# MarsCarrier_PWR.net
KiCad netlist of a schematic drawn in Altium Designer
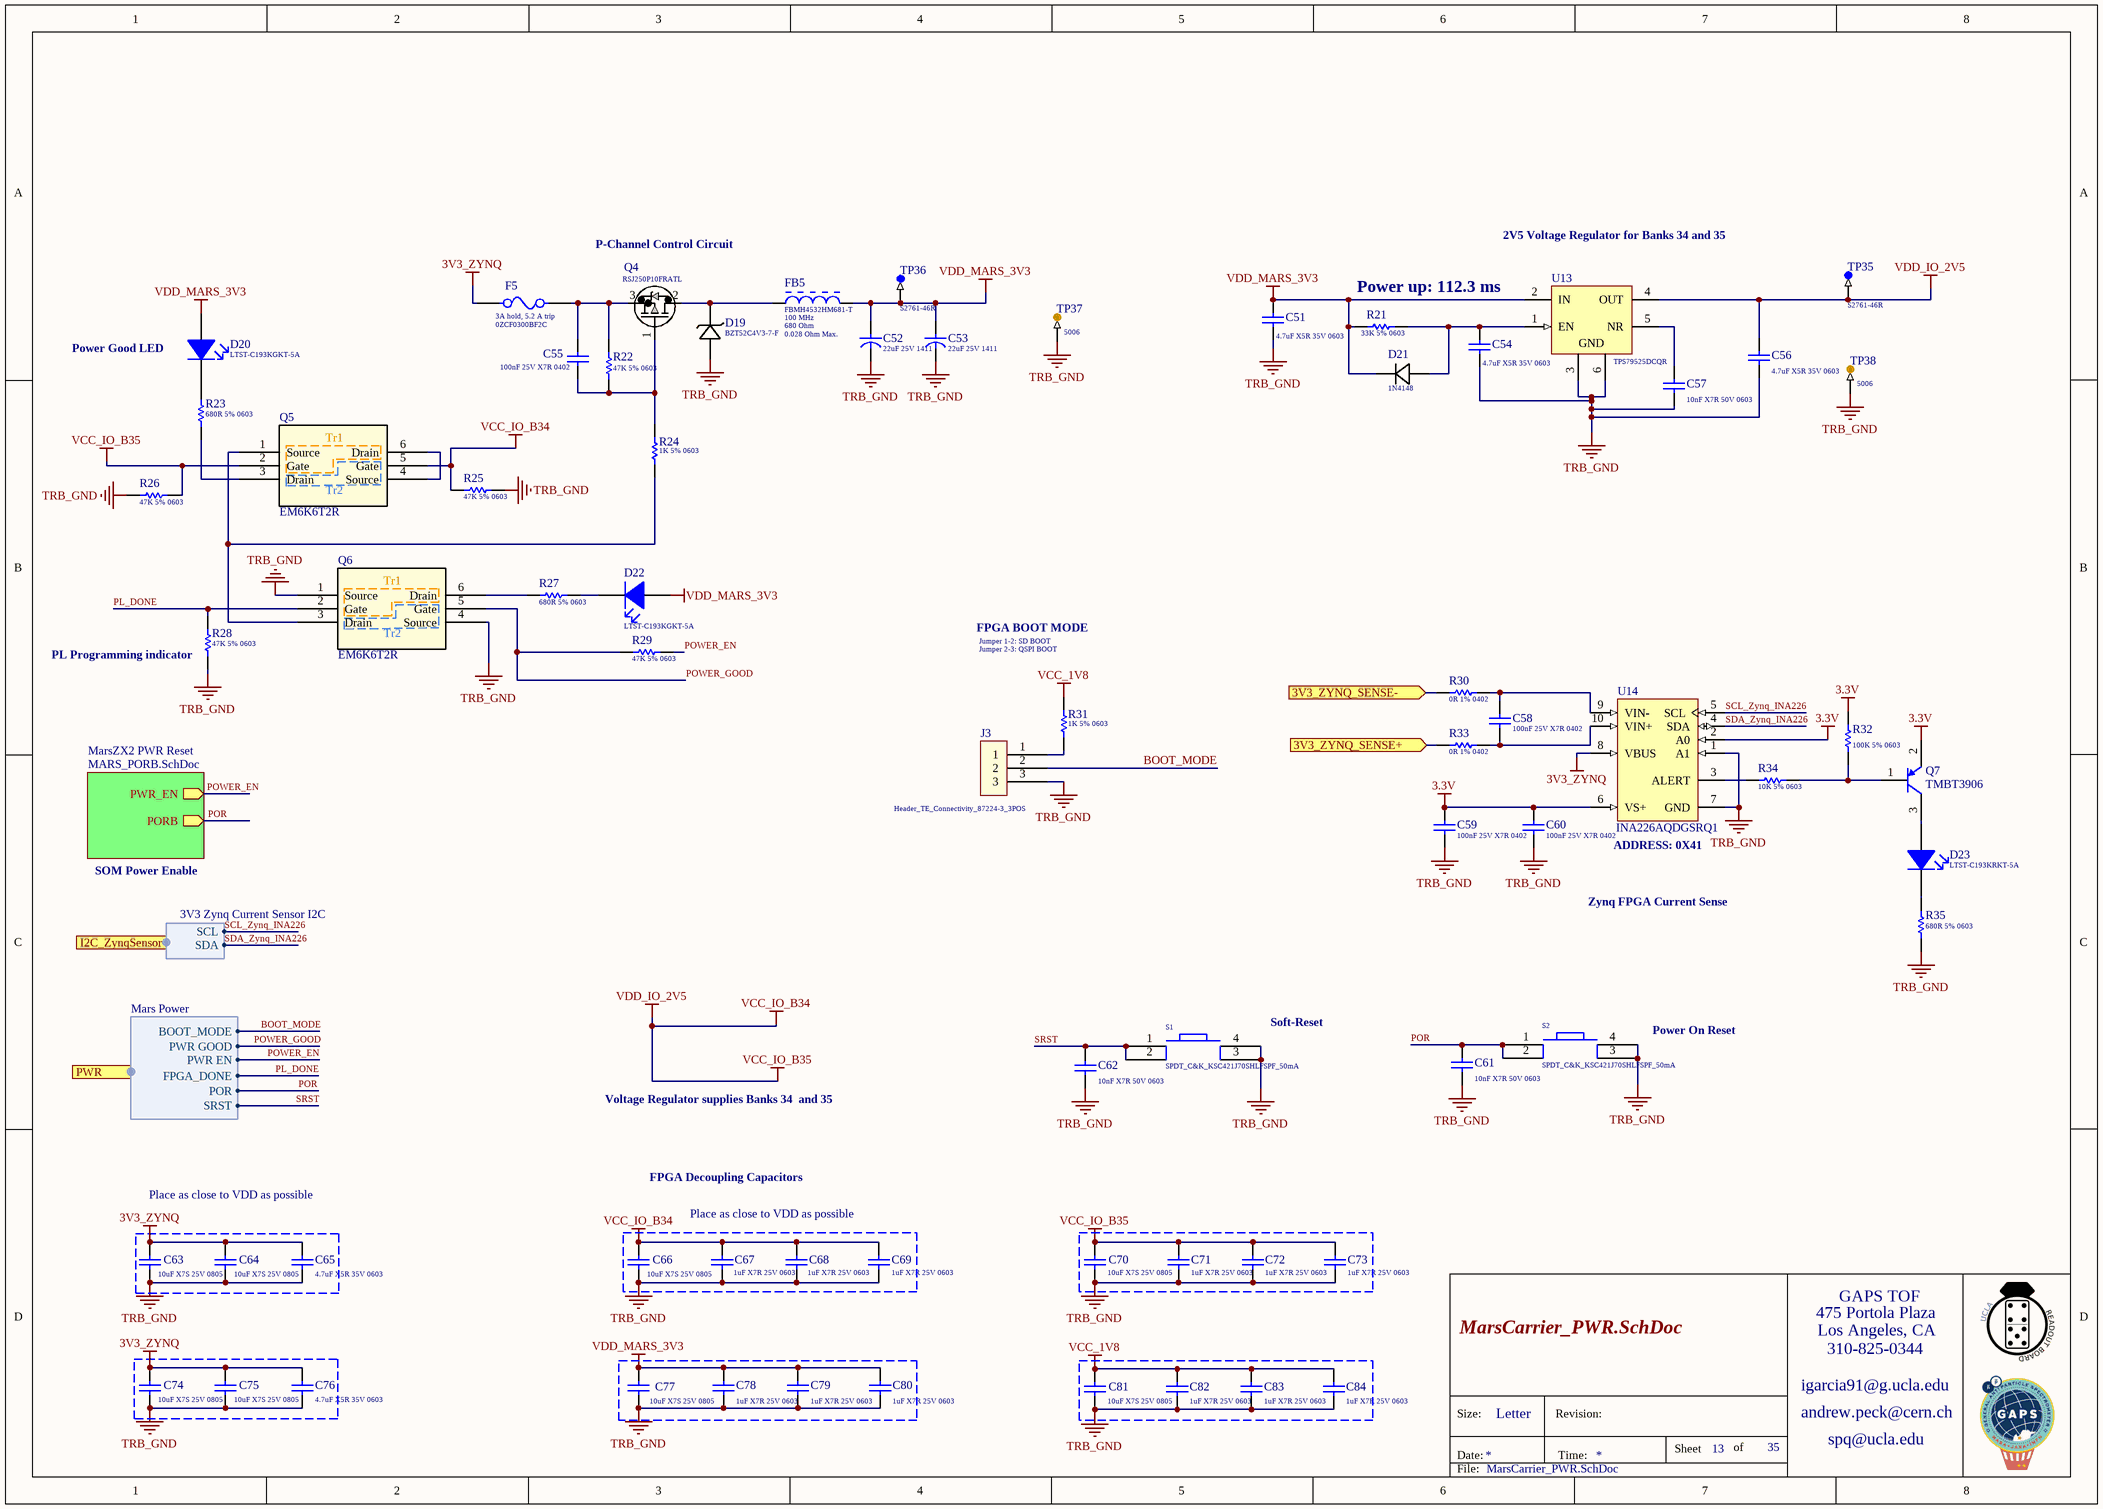
[diagram p0: MarsCarrier_PWR.SchDoc]

(export (version "E")
  (design (tool "Eeschema 10.0.6"))
  (components
    (comp (ref "C51")
      (value "Cap_Murata_ZRB18AR6YA475ME05L_4.7uF")
      (footprint "Cap_Murata_ZRB18AR6YA475ME05L_4.7uF")
      (description "CAP CER 4.7uF 35V X5R 0603")
      (fields (field (name "CAPACITANCE") "4.7uF X5R 35V 0603"))
      (libsource (lib "Cap_Murata_ZRB18AR6YA475ME05L_4.7uF") (part "Cap_Murata_ZRB18AR6YA475ME05L_4.7uF"))
    )
    (comp (ref "C52")
      (value "Cap_Kemet_T521B226M025ATE100_22uF")
      (footprint "Cap_Kemet_T521B226M025ATE100_22uF")
      (description "Tantalum Capacitors - Polymer SMD 25V 22uF 1311 20% ESR=100mOhms")
      (fields (field (name "CAPACITANCE") "22uF 25V 1411"))
      (libsource (lib "Cap_Kemet_T521B226M025ATE100_22uF") (part "Cap_Kemet_T521B226M025ATE100_22uF"))
    )
    (comp (ref "C53")
      (value "Cap_Kemet_T521B226M025ATE100_22uF")
      (footprint "Cap_Kemet_T521B226M025ATE100_22uF")
      (description "Tantalum Capacitors - Polymer SMD 25V 22uF 1311 20% ESR=100mOhms")
      (fields (field (name "CAPACITANCE") "22uF 25V 1411"))
      (libsource (lib "Cap_Kemet_T521B226M025ATE100_22uF") (part "Cap_Kemet_T521B226M025ATE100_22uF"))
    )
    (comp (ref "C54")
      (value "Cap_Murata_ZRB18AR6YA475ME05L_4.7uF")
      (footprint "Cap_Murata_ZRB18AR6YA475ME05L_4.7uF")
      (description "CAP CER 4.7uF 35V X5R 0603")
      (fields (field (name "CAPACITANCE") "4.7uF X5R 35V 0603"))
      (libsource (lib "Cap_Murata_ZRB18AR6YA475ME05L_4.7uF") (part "Cap_Murata_ZRB18AR6YA475ME05L_4.7uF"))
    )
    (comp (ref "C55")
      (value "Cap_Taiyo_Yuden_TMK105B7104KV-FR_100nF")
      (footprint "Cap_Taiyo_Yuden_TMK105B7104KV-FR_100nF")
      (description "CAP CER 100nF 25V X7R 0402")
      (fields (field (name "CAPACITANCE") "100nF 25V X7R 0402"))
      (libsource (lib "Cap_Taiyo_Yuden_TMK105B7104KV-FR_100nF") (part "Cap_Taiyo_Yuden_TMK105B7104KV-FR_100nF"))
    )
    (comp (ref "C56")
      (value "Cap_Murata_ZRB18AR6YA475ME05L_4.7uF")
      (footprint "Cap_Murata_ZRB18AR6YA475ME05L_4.7uF")
      (description "CAP CER 4.7uF 35V X5R 0603")
      (fields (field (name "CAPACITANCE") "4.7uF X5R 35V 0603"))
      (libsource (lib "Cap_Murata_ZRB18AR6YA475ME05L_4.7uF") (part "Cap_Murata_ZRB18AR6YA475ME05L_4.7uF"))
    )
    (comp (ref "C57")
      (value "Cap_Kemet_C0603C103J5RACTU_eec")
      (footprint "Kemet_C0603_0")
      (description "CAP CER 10nF 50V X7R 0603")
      (fields
        (field (name "PART NUMBER") "C0603C103J5RACTU")
        (field (name "MANUFACTURER") "Kemet")
        (field (name "CAPACITANCE") "10nF X7R 50V 0603")
      )
      (libsource (lib "Cap_Kemet_C0603C103J5RACTU_10nF") (part "Cap_Kemet_C0603C103J5RACTU_eec"))
    )
    (comp (ref "C58")
      (value "Cap_Taiyo_Yuden_TMK105B7104KV-FR_100nF")
      (footprint "Cap_Taiyo_Yuden_TMK105B7104KV-FR_100nF")
      (description "CAP CER 100nF 25V X7R 0402")
      (fields (field (name "CAPACITANCE") "100nF 25V X7R 0402"))
      (libsource (lib "Cap_Taiyo_Yuden_TMK105B7104KV-FR_100nF") (part "Cap_Taiyo_Yuden_TMK105B7104KV-FR_100nF"))
    )
    (comp (ref "C59")
      (value "Cap_Taiyo_Yuden_TMK105B7104KV-FR_100nF")
      (footprint "Cap_Taiyo_Yuden_TMK105B7104KV-FR_100nF")
      (description "CAP CER 100nF 25V X7R 0402")
      (fields (field (name "CAPACITANCE") "100nF 25V X7R 0402"))
      (libsource (lib "Cap_Taiyo_Yuden_TMK105B7104KV-FR_100nF") (part "Cap_Taiyo_Yuden_TMK105B7104KV-FR_100nF"))
    )
    (comp (ref "C60")
      (value "Cap_Taiyo_Yuden_TMK105B7104KV-FR_100nF")
      (footprint "Cap_Taiyo_Yuden_TMK105B7104KV-FR_100nF")
      (description "CAP CER 100nF 25V X7R 0402")
      (fields (field (name "CAPACITANCE") "100nF 25V X7R 0402"))
      (libsource (lib "Cap_Taiyo_Yuden_TMK105B7104KV-FR_100nF") (part "Cap_Taiyo_Yuden_TMK105B7104KV-FR_100nF"))
    )
    (comp (ref "C61")
      (value "Cap_Kemet_C0603C103J5RACTU_eec")
      (footprint "Kemet_C0603_0")
      (description "CAP CER 10nF 50V X7R 0603")
      (fields
        (field (name "PART NUMBER") "C0603C103J5RACTU")
        (field (name "MANUFACTURER") "Kemet")
        (field (name "CAPACITANCE") "10nF X7R 50V 0603")
      )
      (libsource (lib "Cap_Kemet_C0603C103J5RACTU_10nF") (part "Cap_Kemet_C0603C103J5RACTU_eec"))
    )
    (comp (ref "C62")
      (value "Cap_Kemet_C0603C103J5RACTU_eec")
      (footprint "Kemet_C0603_0")
      (description "CAP CER 10nF 50V X7R 0603")
      (fields
        (field (name "PART NUMBER") "C0603C103J5RACTU")
        (field (name "MANUFACTURER") "Kemet")
        (field (name "CAPACITANCE") "10nF X7R 50V 0603")
      )
      (libsource (lib "Cap_Kemet_C0603C103J5RACTU_10nF") (part "Cap_Kemet_C0603C103J5RACTU_eec"))
    )
    (comp (ref "C63")
      (value "Cap_Murata_ GRM21BC71E106ME11L_10uF")
      (footprint "Cap_Murata_ GRM21BC71E106ME11L_10uF")
      (description "CAP CER 10uF 25V X7R 0805")
      (fields (field (name "CAPACITANCE") "10uF X7S 25V 0805"))
      (libsource (lib "Cap_Murata_ GRM21BC71E106ME11L_10uF") (part "Cap_Murata_ GRM21BC71E106ME11L_10uF"))
    )
    (comp (ref "C64")
      (value "Cap_Murata_ GRM21BC71E106ME11L_10uF")
      (footprint "Cap_Murata_ GRM21BC71E106ME11L_10uF")
      (description "CAP CER 10uF 25V X7R 0805")
      (fields (field (name "CAPACITANCE") "10uF X7S 25V 0805"))
      (libsource (lib "Cap_Murata_ GRM21BC71E106ME11L_10uF") (part "Cap_Murata_ GRM21BC71E106ME11L_10uF"))
    )
    (comp (ref "C65")
      (value "Cap_Murata_ZRB18AR6YA475ME05L_4.7uF")
      (footprint "Cap_Murata_ZRB18AR6YA475ME05L_4.7uF")
      (description "CAP CER 4.7uF 35V X5R 0603")
      (fields (field (name "CAPACITANCE") "4.7uF X5R 35V 0603"))
      (libsource (lib "Cap_Murata_ZRB18AR6YA475ME05L_4.7uF") (part "Cap_Murata_ZRB18AR6YA475ME05L_4.7uF"))
    )
    (comp (ref "C66")
      (value "Cap_Murata_ GRM21BC71E106ME11L_10uF")
      (footprint "Cap_Murata_ GRM21BC71E106ME11L_10uF")
      (description "CAP CER 10uF 25V X7R 0805")
      (fields (field (name "CAPACITANCE") "10uF X7S 25V 0805"))
      (libsource (lib "Cap_Murata_ GRM21BC71E106ME11L_10uF") (part "Cap_Murata_ GRM21BC71E106ME11L_10uF"))
    )
    (comp (ref "C67")
      (value "Cap_Murata_GCJ188R71E105KA01J_1uF")
      (footprint "Cap_Murata_GCJ188R71E105KA01J_1uF")
      (description "CAP CER 1uF 25V X7R 0603")
      (fields (field (name "CAPACITANCE") "1uF X7R 25V 0603"))
      (libsource (lib "Cap_Murata_GCJ188R71E105KA01J_1uF") (part "Cap_Murata_GCJ188R71E105KA01J_1uF"))
    )
    (comp (ref "C68")
      (value "Cap_Murata_GCJ188R71E105KA01J_1uF")
      (footprint "Cap_Murata_GCJ188R71E105KA01J_1uF")
      (description "CAP CER 1uF 25V X7R 0603")
      (fields (field (name "CAPACITANCE") "1uF X7R 25V 0603"))
      (libsource (lib "Cap_Murata_GCJ188R71E105KA01J_1uF") (part "Cap_Murata_GCJ188R71E105KA01J_1uF"))
    )
    (comp (ref "C69")
      (value "Cap_Murata_GCJ188R71E105KA01J_1uF")
      (footprint "Cap_Murata_GCJ188R71E105KA01J_1uF")
      (description "CAP CER 1uF 25V X7R 0603")
      (fields (field (name "CAPACITANCE") "1uF X7R 25V 0603"))
      (libsource (lib "Cap_Murata_GCJ188R71E105KA01J_1uF") (part "Cap_Murata_GCJ188R71E105KA01J_1uF"))
    )
    (comp (ref "C70")
      (value "Cap_Murata_ GRM21BC71E106ME11L_10uF")
      (footprint "Cap_Murata_ GRM21BC71E106ME11L_10uF")
      (description "CAP CER 10uF 25V X7R 0805")
      (fields (field (name "CAPACITANCE") "10uF X7S 25V 0805"))
      (libsource (lib "Cap_Murata_ GRM21BC71E106ME11L_10uF") (part "Cap_Murata_ GRM21BC71E106ME11L_10uF"))
    )
    (comp (ref "C71")
      (value "Cap_Murata_GCJ188R71E105KA01J_1uF")
      (footprint "Cap_Murata_GCJ188R71E105KA01J_1uF")
      (description "CAP CER 1uF 25V X7R 0603")
      (fields (field (name "CAPACITANCE") "1uF X7R 25V 0603"))
      (libsource (lib "Cap_Murata_GCJ188R71E105KA01J_1uF") (part "Cap_Murata_GCJ188R71E105KA01J_1uF"))
    )
    (comp (ref "C72")
      (value "Cap_Murata_GCJ188R71E105KA01J_1uF")
      (footprint "Cap_Murata_GCJ188R71E105KA01J_1uF")
      (description "CAP CER 1uF 25V X7R 0603")
      (fields (field (name "CAPACITANCE") "1uF X7R 25V 0603"))
      (libsource (lib "Cap_Murata_GCJ188R71E105KA01J_1uF") (part "Cap_Murata_GCJ188R71E105KA01J_1uF"))
    )
    (comp (ref "C73")
      (value "Cap_Murata_GCJ188R71E105KA01J_1uF")
      (footprint "Cap_Murata_GCJ188R71E105KA01J_1uF")
      (description "CAP CER 1uF 25V X7R 0603")
      (fields (field (name "CAPACITANCE") "1uF X7R 25V 0603"))
      (libsource (lib "Cap_Murata_GCJ188R71E105KA01J_1uF") (part "Cap_Murata_GCJ188R71E105KA01J_1uF"))
    )
    (comp (ref "C74")
      (value "Cap_Murata_ GRM21BC71E106ME11L_10uF")
      (footprint "Cap_Murata_ GRM21BC71E106ME11L_10uF")
      (description "CAP CER 10uF 25V X7R 0805")
      (fields (field (name "CAPACITANCE") "10uF X7S 25V 0805"))
      (libsource (lib "Cap_Murata_ GRM21BC71E106ME11L_10uF") (part "Cap_Murata_ GRM21BC71E106ME11L_10uF"))
    )
    (comp (ref "C75")
      (value "Cap_Murata_ GRM21BC71E106ME11L_10uF")
      (footprint "Cap_Murata_ GRM21BC71E106ME11L_10uF")
      (description "CAP CER 10uF 25V X7R 0805")
      (fields (field (name "CAPACITANCE") "10uF X7S 25V 0805"))
      (libsource (lib "Cap_Murata_ GRM21BC71E106ME11L_10uF") (part "Cap_Murata_ GRM21BC71E106ME11L_10uF"))
    )
    (comp (ref "C76")
      (value "Cap_Murata_ZRB18AR6YA475ME05L_4.7uF")
      (footprint "Cap_Murata_ZRB18AR6YA475ME05L_4.7uF")
      (description "CAP CER 4.7uF 35V X5R 0603")
      (fields (field (name "CAPACITANCE") "4.7uF X5R 35V 0603"))
      (libsource (lib "Cap_Murata_ZRB18AR6YA475ME05L_4.7uF") (part "Cap_Murata_ZRB18AR6YA475ME05L_4.7uF"))
    )
    (comp (ref "C77")
      (value "Cap_Murata_ GRM21BC71E106ME11L_10uF")
      (footprint "Cap_Murata_ GRM21BC71E106ME11L_10uF")
      (description "CAP CER 10uF 25V X7R 0805")
      (fields (field (name "CAPACITANCE") "10uF X7S 25V 0805"))
      (libsource (lib "Cap_Murata_ GRM21BC71E106ME11L_10uF") (part "Cap_Murata_ GRM21BC71E106ME11L_10uF"))
    )
    (comp (ref "C78")
      (value "Cap_Murata_GCJ188R71E105KA01J_1uF")
      (footprint "Cap_Murata_GCJ188R71E105KA01J_1uF")
      (description "CAP CER 1uF 25V X7R 0603")
      (fields (field (name "CAPACITANCE") "1uF X7R 25V 0603"))
      (libsource (lib "Cap_Murata_GCJ188R71E105KA01J_1uF") (part "Cap_Murata_GCJ188R71E105KA01J_1uF"))
    )
    (comp (ref "C79")
      (value "Cap_Murata_GCJ188R71E105KA01J_1uF")
      (footprint "Cap_Murata_GCJ188R71E105KA01J_1uF")
      (description "CAP CER 1uF 25V X7R 0603")
      (fields (field (name "CAPACITANCE") "1uF X7R 25V 0603"))
      (libsource (lib "Cap_Murata_GCJ188R71E105KA01J_1uF") (part "Cap_Murata_GCJ188R71E105KA01J_1uF"))
    )
    (comp (ref "C80")
      (value "Cap_Murata_GCJ188R71E105KA01J_1uF")
      (footprint "Cap_Murata_GCJ188R71E105KA01J_1uF")
      (description "CAP CER 1uF 25V X7R 0603")
      (fields (field (name "CAPACITANCE") "1uF X7R 25V 0603"))
      (libsource (lib "Cap_Murata_GCJ188R71E105KA01J_1uF") (part "Cap_Murata_GCJ188R71E105KA01J_1uF"))
    )
    (comp (ref "C81")
      (value "Cap_Murata_ GRM21BC71E106ME11L_10uF")
      (footprint "Cap_Murata_ GRM21BC71E106ME11L_10uF")
      (description "CAP CER 10uF 25V X7R 0805")
      (fields (field (name "CAPACITANCE") "10uF X7S 25V 0805"))
      (libsource (lib "Cap_Murata_ GRM21BC71E106ME11L_10uF") (part "Cap_Murata_ GRM21BC71E106ME11L_10uF"))
    )
    (comp (ref "C82")
      (value "Cap_Murata_GCJ188R71E105KA01J_1uF")
      (footprint "Cap_Murata_GCJ188R71E105KA01J_1uF")
      (description "CAP CER 1uF 25V X7R 0603")
      (fields (field (name "CAPACITANCE") "1uF X7R 25V 0603"))
      (libsource (lib "Cap_Murata_GCJ188R71E105KA01J_1uF") (part "Cap_Murata_GCJ188R71E105KA01J_1uF"))
    )
    (comp (ref "C83")
      (value "Cap_Murata_GCJ188R71E105KA01J_1uF")
      (footprint "Cap_Murata_GCJ188R71E105KA01J_1uF")
      (description "CAP CER 1uF 25V X7R 0603")
      (fields (field (name "CAPACITANCE") "1uF X7R 25V 0603"))
      (libsource (lib "Cap_Murata_GCJ188R71E105KA01J_1uF") (part "Cap_Murata_GCJ188R71E105KA01J_1uF"))
    )
    (comp (ref "C84")
      (value "Cap_Murata_GCJ188R71E105KA01J_1uF")
      (footprint "Cap_Murata_GCJ188R71E105KA01J_1uF")
      (description "CAP CER 1uF 25V X7R 0603")
      (fields (field (name "CAPACITANCE") "1uF X7R 25V 0603"))
      (libsource (lib "Cap_Murata_GCJ188R71E105KA01J_1uF") (part "Cap_Murata_GCJ188R71E105KA01J_1uF"))
    )
    (comp (ref "D19")
      (value "BZT52C4V3-7-F")
      (footprint "SOD123")
      (description "Zener Diodes 500mW 4.3V Zener AEC-Q101 Qualified")
      (fields (field (name "SERIES") "BZT52C4V3-7-F"))
      (libsource (lib "4v3_zener_BZT52C4V3-7-F") (part "BZT52C4V3-7-F"))
    )
    (comp (ref "D20")
      (value "Led_Lite-On_LTST-C193KGKT-5A_Green")
      (footprint "Led_Lite-On_LTST-C193KGKT-5A_Green")
      (description "Standard LEDs - SMD Green 470nm 28mcd 20mA")
      (fields (field (name "SERIES") "LTST-C193KGKT-5A"))
      (libsource (lib "Led_Lite-On_LTST-C193KGKT-5A_Green") (part "Led_Lite-On_LTST-C193KGKT-5A_Green"))
    )
    (comp (ref "D21")
      (value "Diode_ON_Semiconductor_1N4148WT_300mA")
      (footprint "Diode_ON_Semiconductor_1N4148WT_300mA")
      (description "Diodes - General Purpose, Power, Switching SINGLE JUNC. 75V 4.0NS COMP")
      (fields (field (name "SERIES") "1N4148"))
      (libsource (lib "Diode_ON_Semiconductor_1N4148WT_300mA") (part "Diode_ON_Semiconductor_1N4148WT_300mA"))
    )
    (comp (ref "D22")
      (value "Led_Lite-On_LTST-C193KGKT-5A_Green")
      (footprint "Led_Lite-On_LTST-C193KGKT-5A_Green")
      (description "Standard LEDs - SMD Green 470nm 28mcd 20mA")
      (fields (field (name "SERIES") "LTST-C193KGKT-5A"))
      (libsource (lib "Led_Lite-On_LTST-C193KGKT-5A_Green") (part "Led_Lite-On_LTST-C193KGKT-5A_Green"))
    )
    (comp (ref "D23")
      (value "LTST-C193KRKT-5A")
      (footprint "Led_Lite-On_LTST-C193KGKT-5A_Red")
      (description "Standard LEDs - SMD Red 470nm 28mcd 20mA")
      (fields (field (name "SERIES") "LTST-C193KRKT-5A"))
      (libsource (lib "Led_Lite-On_LTST-C193KGKT-5A_Red") (part "Led_Lite-On_LTST-C193KGKT-5A_Red"))
    )
    (comp (ref "F5")
      (value "3A hold, 5.2 A trip")
      (footprint "Bel_0ZCF_MFG")
      (description "Resettable Fuses - PPTC 3A 24V PPTC 2920 SMD")
      (fields (field (name "SERIES") "0ZCF0300BF2C"))
      (libsource (lib "Fuse_Bel_0ZCF0300BF2C_3A_hold") (part "0ZCF0300BF2C"))
    )
    (comp (ref "FB5")
      (value "FBMH4532HM681-T")
      (footprint "TAYO-FBMH4532-2_V")
      (fields
        (field (name "PARTNUMBER") "FBMH4532HM681-T")
        (field (name "MANUFACTURER") "Taiyo Yuden")
        (field (name "MEASURING FREQUENCY") "100 MHz")
        (field (name "NOMINAL IMPEDANCE") "680 Ohm")
        (field (name "DC RESISTANCE") "0.028 Ohm Max.")
      )
      (libsource (lib "Taiyo_Yuden_FBMH4532HM681") (part "FBMH4532HM681-T"))
    )
    (comp (ref "J3")
      (value "Header_TE_Connectivity_87224-3_3POS")
      (footprint "Header_TE_Connectivity_87224-3_3POS")
      (description "Headers & Wire Housings UNSHRD VERT SNGL 3")
      (libsource (lib "Header_TE_Connectivity_87224-3_3POS") (part "Header_TE_Connectivity_87224-3_3POS"))
    )
    (comp (ref "Q4")
      (value "Mos_ROHM_RSJ250P10FRATL_25A")
      (footprint "Mos_ROHM_RSJ250P10FRATL_25A")
      (description "MOSFET Pch -100V Vds -25A 0.05Rds(on) 60Qg")
      (fields (field (name "SERIES") "RSJ250P10FRATL"))
      (libsource (lib "Mos_ROHM_RSJ250P10FRATL_25A") (part "Mos_ROHM_RSJ250P10FRATL_25A"))
    )
    (comp (ref "Q5")
      (value "EM6K6T2R")
      (footprint "TRANS_EM6_ROM")
      (description "MOSFET Small Signal Dual N-CH 20V .3A .15W")
      (libsource (lib "Trans_NFET_ROHM_EM6K6T2R") (part "EM6K6T2R"))
    )
    (comp (ref "Q6")
      (value "EM6K6T2R")
      (footprint "TRANS_EM6_ROM")
      (description "MOSFET Small Signal Dual N-CH 20V .3A .15W")
      (libsource (lib "Trans_NFET_ROHM_EM6K6T2R") (part "EM6K6T2R"))
    )
    (comp (ref "Q7")
      (value "BJT_PNP_Toshiba_TMBT3906")
      (footprint "BJT_PNP_Toshiba_TMBT3906")
      (description "Bipolar Transistors - BJT Transistor for Low Freq. Amplification")
      (fields (field (name "SERIES") "TMBT3906") (field (name "MANUFACTURER") "Toshiba"))
      (libsource (lib "BJT_PNP_Toshiba_TMBT3906") (part "BJT_PNP_Toshiba_TMBT3906"))
    )
    (comp (ref "R21")
      (value "33K 5% 0603")
      (footprint "RESC0603(1608)_L")
      (description "33K 0.1W 5% 0603 (1608 Metric)  SMD")
      (fields (field (name "TOLERANCE") "5 %") (field (name "POWER") "0.1 W"))
      (libsource (lib "Altium Content Vault") (part "RES"))
    )
    (comp (ref "R22")
      (value "47K 5% 0603")
      (footprint "RESC0603(1608)_L")
      (description "47K 0.1W 5% 0603 (1608 Metric)  SMD")
      (fields (field (name "TOLERANCE") "5 %") (field (name "POWER") "0.1 W"))
      (libsource (lib "Altium Content Vault") (part "RES"))
    )
    (comp (ref "R23")
      (value "680R 5% 0603")
      (footprint "RESC0603(1608)_L")
      (description "680R 0.1W 5% 0603 (1608 Metric)  SMD")
      (fields (field (name "TOLERANCE") "5 %") (field (name "POWER") "0.1 W"))
      (libsource (lib "Altium Content Vault") (part "RES"))
    )
    (comp (ref "R24")
      (value "1K 5% 0603")
      (footprint "RESC0603(1608)_L")
      (description "1K 0.1W 5% 0603 (1608 Metric)  SMD")
      (fields (field (name "TOLERANCE") "5 %") (field (name "POWER") "0.1 W"))
      (libsource (lib "Altium Content Vault") (part "RES"))
    )
    (comp (ref "R25")
      (value "47K 5% 0603")
      (footprint "RESC0603(1608)_L")
      (description "47K 0.1W 5% 0603 (1608 Metric)  SMD")
      (fields (field (name "TOLERANCE") "5 %") (field (name "POWER") "0.1 W"))
      (libsource (lib "Altium Content Vault") (part "RES"))
    )
    (comp (ref "R26")
      (value "47K 5% 0603")
      (footprint "RESC0603(1608)_L")
      (description "47K 0.1W 5% 0603 (1608 Metric)  SMD")
      (fields (field (name "TOLERANCE") "5 %") (field (name "POWER") "0.1 W"))
      (libsource (lib "Altium Content Vault") (part "RES"))
    )
    (comp (ref "R27")
      (value "680R 5% 0603")
      (footprint "RESC0603(1608)_L")
      (description "680R 0.1W 5% 0603 (1608 Metric)  SMD")
      (fields (field (name "TOLERANCE") "5 %") (field (name "POWER") "0.1 W"))
      (libsource (lib "Altium Content Vault") (part "RES"))
    )
    (comp (ref "R28")
      (value "47K 5% 0603")
      (footprint "RESC0603(1608)_L")
      (description "47K 0.1W 5% 0603 (1608 Metric)  SMD")
      (fields (field (name "TOLERANCE") "5 %") (field (name "POWER") "0.1 W"))
      (libsource (lib "Altium Content Vault") (part "RES"))
    )
    (comp (ref "R29")
      (value "47K 5% 0603")
      (footprint "RESC0603(1608)_L")
      (description "47K 0.1W 5% 0603 (1608 Metric)  SMD")
      (fields (field (name "TOLERANCE") "5 %") (field (name "POWER") "0.1 W"))
      (libsource (lib "Altium Content Vault") (part "RES"))
    )
    (comp (ref "R30")
      (value "Res_Vishay_CRCW04020000Z0EDC_0_Ohm")
      (footprint "Res_Vishay_CRCW04020000Z0EDC_0_Ohm")
      (description "0R 0.062W 1% 0402 (1005 Metric)  SMD")
      (fields (field (name "RESISTANCE") "0R 1% 0402"))
      (libsource (lib "Res_Vishay_CRCW04020000Z0EDC_0_Ohm") (part "Res_Vishay_CRCW04020000Z0EDC_0_Ohm"))
    )
    (comp (ref "R31")
      (value "1K 5% 0603")
      (footprint "RESC0603(1608)_L")
      (description "1K 0.1W 5% 0603 (1608 Metric)  SMD")
      (fields (field (name "TOLERANCE") "5 %") (field (name "POWER") "0.1 W"))
      (libsource (lib "Altium Content Vault") (part "RES"))
    )
    (comp (ref "R32")
      (value "100K 5% 0603")
      (footprint "RESC0603(1608)_N")
      (description "100K 0.1W 5% 0603 (1608 Metric)  SMD")
      (fields (field (name "TOLERANCE") "5 %") (field (name "POWER") "0.1 W"))
      (libsource (lib "Altium Content Vault") (part "RES"))
    )
    (comp (ref "R33")
      (value "Res_Vishay_CRCW04020000Z0EDC_0_Ohm")
      (footprint "Res_Vishay_CRCW04020000Z0EDC_0_Ohm")
      (description "0R 0.062W 1% 0402 (1005 Metric)  SMD")
      (fields (field (name "RESISTANCE") "0R 1% 0402"))
      (libsource (lib "Res_Vishay_CRCW04020000Z0EDC_0_Ohm") (part "Res_Vishay_CRCW04020000Z0EDC_0_Ohm"))
    )
    (comp (ref "R34")
      (value "10K 5% 0603")
      (footprint "RESC0603(1608)_L")
      (description "10K 0.1W 5% 0603 (1608 Metric)  SMD")
      (fields (field (name "TOLERANCE") "5 %") (field (name "POWER") "0.1 W"))
      (libsource (lib "Altium Content Vault") (part "RES"))
    )
    (comp (ref "R35")
      (value "680R 5% 0603")
      (footprint "RESC0603(1608)_L")
      (description "680R 0.1W 5% 0603 (1608 Metric)  SMD")
      (fields (field (name "TOLERANCE") "5 %") (field (name "POWER") "0.1 W"))
      (libsource (lib "Altium Content Vault") (part "RES"))
    )
    (comp (ref "S1")
      (value "SPDT_C&K_KSC421J70SHLFSPF_50mA")
      (footprint "SPDT_C&K_KSC421J70SHLFSPF_50mA")
      (description "Tactile Switches Tact 6.2 x 6.2, 5.1 mm H, 1.7N, J leads, Potting Friendly, IP67")
      (libsource (lib "SPDT_C&K_KSC421J70SHLFSPF_50mA") (part "SPDT_C&K_KSC421J70SHLFSPF_50mA"))
    )
    (comp (ref "S2")
      (value "SPDT_C&K_KSC421J70SHLFSPF_50mA")
      (footprint "SPDT_C&K_KSC421J70SHLFSPF_50mA")
      (description "Tactile Switches Tact 6.2 x 6.2, 5.1 mm H, 1.7N, J leads, Potting Friendly, IP67")
      (libsource (lib "SPDT_C&K_KSC421J70SHLFSPF_50mA") (part "SPDT_C&K_KSC421J70SHLFSPF_50mA"))
    )
    (comp (ref "TP35")
      (value "TP_Harwin_S2761_46R")
      (footprint "TP_Harwin_S2761_46R")
      (description "Circuit Board Hardware - PCB SMT Mini Test Terminal, Reel")
      (fields (field (name "SERIES") "S2761-46R"))
      (libsource (lib "TP_Harwin_S2761_46R") (part "TP_Harwin_S2761_46R"))
    )
    (comp (ref "TP36")
      (value "TP_Harwin_S2761_46R")
      (footprint "TP_Harwin_S2761_46R")
      (description "Circuit Board Hardware - PCB SMT Mini Test Terminal, Reel")
      (fields (field (name "SERIES") "S2761-46R"))
      (libsource (lib "TP_Harwin_S2761_46R") (part "TP_Harwin_S2761_46R"))
    )
    (comp (ref "TP37")
      (value "TP_Keystone_Electronics_5006")
      (footprint "TP_Keystone_Electronics_5006")
      (description "Circuit Board Hardware - PCB TEST POINT BLK .063")
      (fields (field (name "SERIES") "5006"))
      (libsource (lib "TP_Keystone_Electronics_5006") (part "TP_Keystone_Electronics_5006"))
    )
    (comp (ref "TP38")
      (value "TP_Keystone_Electronics_5006")
      (footprint "TP_Keystone_Electronics_5006")
      (description "Circuit Board Hardware - PCB TEST POINT BLK .063")
      (fields (field (name "SERIES") "5006"))
      (libsource (lib "TP_Keystone_Electronics_5006") (part "TP_Keystone_Electronics_5006"))
    )
    (comp (ref "U13")
      (value "TPS79525DCQR")
      (footprint "DCQ0006A_L")
      (fields (field (name "MANUFACTURER") "Texas Instruments"))
      (libsource (lib "TPS79525DCQR") (part "CMP-0395-00444-2"))
    )
    (comp (ref "U14")
      (value "INA226AQDGSRQ1")
      (footprint "INA226AQDGSRQ1")
      (libsource (lib "INA226AQDGSRQ1") (part "INA226AQDGSRQ1"))
    )
  )
  (nets
    (net (code "8") (name "/3V3_ZYNQ_SENSE+") (class "Default")
      (node (ref "R33") (pin "1") (pinfunction "1_1") (pintype "passive"))
    )
    (net (code "9") (name "/3V3_ZYNQ_SENSE-") (class "Default")
      (node (ref "R30") (pin "1") (pinfunction "1_1") (pintype "passive"))
    )
    (net (code "10") (name "/BOOT_MODE") (class "Default")
      (node (ref "J3") (pin "2") (pinfunction "2_2") (pintype "passive"))
    )
    (net (code "11") (name "/PL_DONE") (class "Default")
      (node (ref "Q6") (pin "2") (pinfunction "Gate_2") (pintype "passive"))
      (node (ref "R28") (pin "2") (pinfunction "2_2") (pintype "passive"))
    )
    (net (code "12") (name "/POR") (class "Default")
      (node (ref "C61") (pin "1") (pinfunction "1_1") (pintype "passive"))
      (node (ref "S2") (pin "1") (pintype "passive"))
      (node (ref "S2") (pin "2") (pintype "passive"))
    )
    (net (code "13") (name "/POWER_EN") (class "Default")
      (node (ref "R29") (pin "1") (pinfunction "1_1") (pintype "passive"))
    )
    (net (code "14") (name "/POWER_GOOD") (class "Default")
      (node (ref "Q6") (pin "5") (pinfunction "Gate_5") (pintype "passive"))
      (node (ref "R29") (pin "2") (pinfunction "2_2") (pintype "passive"))
    )
    (net (code "15") (name "/SCL_Zynq_INA226") (class "Default")
      (node (ref "U14") (pin "5") (pinfunction "SCL_5") (pintype "input"))
    )
    (net (code "16") (name "/SDA_Zynq_INA226") (class "Default")
      (node (ref "U14") (pin "4") (pinfunction "SDA_4") (pintype "bidirectional"))
    )
    (net (code "17") (name "/SRST") (class "Default")
      (node (ref "C62") (pin "1") (pinfunction "1_1") (pintype "passive"))
      (node (ref "S1") (pin "1") (pintype "passive"))
      (node (ref "S1") (pin "2") (pintype "passive"))
    )
    (net (code "20") (name "3.3V") (class "Default")
      (node (ref "C59") (pin "2") (pinfunction "2_2") (pintype "passive"))
      (node (ref "C60") (pin "2") (pinfunction "2_2") (pintype "passive"))
      (node (ref "Q7") (pin "2") (pinfunction "E_2") (pintype "passive"))
      (node (ref "R32") (pin "2") (pinfunction "2_2") (pintype "passive"))
      (node (ref "U14") (pin "2") (pinfunction "A0_2") (pintype "input"))
      (node (ref "U14") (pin "6") (pinfunction "VS+_6") (pintype "input"))
    )
    (net (code "21") (name "3V3_ZYNQ") (class "Default")
      (node (ref "C63") (pin "1") (pinfunction "1_1") (pintype "passive"))
      (node (ref "C64") (pin "1") (pinfunction "1_1") (pintype "passive"))
      (node (ref "C65") (pin "1") (pinfunction "1_1") (pintype "passive"))
      (node (ref "C74") (pin "1") (pinfunction "1_1") (pintype "passive"))
      (node (ref "C75") (pin "1") (pinfunction "1_1") (pintype "passive"))
      (node (ref "C76") (pin "1") (pinfunction "1_1") (pintype "passive"))
      (node (ref "F5") (pin "1") (pinfunction "1_1") (pintype "passive"))
      (node (ref "U14") (pin "8") (pinfunction "VBUS_8") (pintype "input"))
    )
    (net (code "22") (name "Net-(D20-K)") (class "Default")
      (node (ref "D20") (pin "1") (pinfunction "K_1") (pintype "passive"))
      (node (ref "R23") (pin "2") (pinfunction "2_2") (pintype "passive"))
    )
    (net (code "23") (name "Net-(D22-K)") (class "Default")
      (node (ref "D22") (pin "1") (pinfunction "K_1") (pintype "passive"))
      (node (ref "R27") (pin "1") (pinfunction "1_1") (pintype "passive"))
    )
    (net (code "24") (name "Net-(D23-A)") (class "Default")
      (node (ref "D23") (pin "2") (pinfunction "A_2") (pintype "passive"))
      (node (ref "Q7") (pin "3") (pinfunction "C_3") (pintype "passive"))
    )
    (net (code "25") (name "Net-(D23-K)") (class "Default")
      (node (ref "D23") (pin "1") (pinfunction "K_1") (pintype "passive"))
      (node (ref "R35") (pin "2") (pinfunction "2_2") (pintype "passive"))
    )
    (net (code "26") (name "Net-(J3-Pad1)") (class "Default")
      (node (ref "J3") (pin "1") (pinfunction "1_1") (pintype "passive"))
      (node (ref "R31") (pin "1") (pinfunction "1_1") (pintype "passive"))
    )
    (net (code "27") (name "Net-(Q4-D)") (class "Default")
      (node (ref "D19") (pin "1") (pinfunction "1_1") (pintype "passive"))
      (node (ref "FB5") (pin "1") (pinfunction "1_1") (pintype "passive"))
      (node (ref "Q4") (pin "2") (pinfunction "D_2") (pintype "passive"))
    )
    (net (code "28") (name "Net-(Q4-G)") (class "Default")
      (node (ref "C55") (pin "1") (pinfunction "1_1") (pintype "passive"))
      (node (ref "Q4") (pin "1") (pinfunction "G_1") (pintype "passive"))
      (node (ref "R22") (pin "1") (pinfunction "1_1") (pintype "passive"))
      (node (ref "R24") (pin "2") (pinfunction "2_2") (pintype "passive"))
    )
    (net (code "29") (name "Net-(Q4-S)") (class "Default")
      (node (ref "C55") (pin "2") (pinfunction "2_2") (pintype "passive"))
      (node (ref "F5") (pin "2") (pinfunction "2_2") (pintype "passive"))
      (node (ref "Q4") (pin "3") (pinfunction "S_3") (pintype "passive"))
      (node (ref "R22") (pin "2") (pinfunction "2_2") (pintype "passive"))
    )
    (net (code "30") (name "Net-(Q5-Drain-Pad3)") (class "Default")
      (node (ref "Q5") (pin "3") (pinfunction "Drain_3") (pintype "passive"))
      (node (ref "R23") (pin "1") (pinfunction "1_1") (pintype "passive"))
    )
    (net (code "31") (name "Net-(Q5-Drain-Pad6)") (class "Default")
      (node (ref "Q5") (pin "4") (pinfunction "Source_4") (pintype "passive"))
      (node (ref "Q5") (pin "6") (pinfunction "Drain_6") (pintype "passive"))
    )
    (net (code "32") (name "Net-(Q5-Source-Pad1)") (class "Default")
      (node (ref "Q5") (pin "1") (pinfunction "Source_1") (pintype "passive"))
      (node (ref "Q6") (pin "3") (pinfunction "Drain_3") (pintype "passive"))
      (node (ref "R24") (pin "1") (pinfunction "1_1") (pintype "passive"))
    )
    (net (code "33") (name "Net-(Q6-Drain-Pad6)") (class "Default")
      (node (ref "Q6") (pin "6") (pinfunction "Drain_6") (pintype "passive"))
      (node (ref "R27") (pin "2") (pinfunction "2_2") (pintype "passive"))
    )
    (net (code "34") (name "Net-(Q7-B)") (class "Default")
      (node (ref "Q7") (pin "1") (pinfunction "B_1") (pintype "passive"))
      (node (ref "R32") (pin "1") (pinfunction "1_1") (pintype "passive"))
      (node (ref "R34") (pin "1") (pinfunction "1_1") (pintype "passive"))
    )
    (net (code "35") (name "Net-(U13-EN)") (class "Default")
      (node (ref "C54") (pin "2") (pinfunction "2_2") (pintype "passive"))
      (node (ref "D21") (pin "2") (pinfunction "2_2") (pintype "passive"))
      (node (ref "R21") (pin "2") (pinfunction "2_2") (pintype "passive"))
      (node (ref "U13") (pin "1") (pinfunction "EN_1") (pintype "input"))
    )
    (net (code "36") (name "Net-(U13-NR)") (class "Default")
      (node (ref "C57") (pin "1") (pinfunction "1_1") (pintype "passive"))
      (node (ref "U13") (pin "5") (pinfunction "NR_5") (pintype "passive"))
    )
    (net (code "37") (name "Net-(U14-ALERT)") (class "Default")
      (node (ref "R34") (pin "2") (pinfunction "2_2") (pintype "passive"))
      (node (ref "U14") (pin "3") (pinfunction "ALERT_3") (pintype "open_collector"))
    )
    (net (code "38") (name "Net-(U14-VIN+)") (class "Default")
      (node (ref "C58") (pin "1") (pinfunction "1_1") (pintype "passive"))
      (node (ref "R33") (pin "2") (pinfunction "2_2") (pintype "passive"))
      (node (ref "U14") (pin "10") (pinfunction "VIN+_10") (pintype "input"))
    )
    (net (code "39") (name "Net-(U14-VIN-)") (class "Default")
      (node (ref "C58") (pin "2") (pinfunction "2_2") (pintype "passive"))
      (node (ref "R30") (pin "2") (pinfunction "2_2") (pintype "passive"))
      (node (ref "U14") (pin "9") (pinfunction "VIN-_9") (pintype "input"))
    )
    (net (code "40") (name "TRB_GND") (class "Default")
      (node (ref "C51") (pin "1") (pinfunction "1_1") (pintype "passive"))
      (node (ref "C52") (pin "2") (pinfunction "2_2") (pintype "passive"))
      (node (ref "C53") (pin "2") (pinfunction "2_2") (pintype "passive"))
      (node (ref "C54") (pin "1") (pinfunction "1_1") (pintype "passive"))
      (node (ref "C56") (pin "1") (pinfunction "1_1") (pintype "passive"))
      (node (ref "C57") (pin "2") (pinfunction "2_2") (pintype "passive"))
      (node (ref "C59") (pin "1") (pinfunction "1_1") (pintype "passive"))
      (node (ref "C60") (pin "1") (pinfunction "1_1") (pintype "passive"))
      (node (ref "C61") (pin "2") (pinfunction "2_2") (pintype "passive"))
      (node (ref "C62") (pin "2") (pinfunction "2_2") (pintype "passive"))
      (node (ref "C63") (pin "2") (pinfunction "2_2") (pintype "passive"))
      (node (ref "C64") (pin "2") (pinfunction "2_2") (pintype "passive"))
      (node (ref "C65") (pin "2") (pinfunction "2_2") (pintype "passive"))
      (node (ref "C66") (pin "2") (pinfunction "2_2") (pintype "passive"))
      (node (ref "C67") (pin "1") (pinfunction "1_1") (pintype "passive"))
      (node (ref "C68") (pin "1") (pinfunction "1_1") (pintype "passive"))
      (node (ref "C69") (pin "1") (pinfunction "1_1") (pintype "passive"))
      (node (ref "C70") (pin "2") (pinfunction "2_2") (pintype "passive"))
      (node (ref "C71") (pin "1") (pinfunction "1_1") (pintype "passive"))
      (node (ref "C72") (pin "1") (pinfunction "1_1") (pintype "passive"))
      (node (ref "C73") (pin "1") (pinfunction "1_1") (pintype "passive"))
      (node (ref "C74") (pin "2") (pinfunction "2_2") (pintype "passive"))
      (node (ref "C75") (pin "2") (pinfunction "2_2") (pintype "passive"))
      (node (ref "C76") (pin "2") (pinfunction "2_2") (pintype "passive"))
      (node (ref "C77") (pin "2") (pinfunction "2_2") (pintype "passive"))
      (node (ref "C78") (pin "1") (pinfunction "1_1") (pintype "passive"))
      (node (ref "C79") (pin "1") (pinfunction "1_1") (pintype "passive"))
      (node (ref "C80") (pin "1") (pinfunction "1_1") (pintype "passive"))
      (node (ref "C81") (pin "2") (pinfunction "2_2") (pintype "passive"))
      (node (ref "C82") (pin "1") (pinfunction "1_1") (pintype "passive"))
      (node (ref "C83") (pin "1") (pinfunction "1_1") (pintype "passive"))
      (node (ref "C84") (pin "1") (pinfunction "1_1") (pintype "passive"))
      (node (ref "D19") (pin "2") (pinfunction "2_2") (pintype "passive"))
      (node (ref "J3") (pin "3") (pinfunction "3_3") (pintype "passive"))
      (node (ref "Q6") (pin "1") (pinfunction "Source_1") (pintype "passive"))
      (node (ref "Q6") (pin "4") (pinfunction "Source_4") (pintype "passive"))
      (node (ref "R25") (pin "2") (pinfunction "2_2") (pintype "passive"))
      (node (ref "R26") (pin "2") (pinfunction "2_2") (pintype "passive"))
      (node (ref "R28") (pin "1") (pinfunction "1_1") (pintype "passive"))
      (node (ref "R35") (pin "1") (pinfunction "1_1") (pintype "passive"))
      (node (ref "S1") (pin "3") (pintype "passive"))
      (node (ref "S1") (pin "4") (pintype "passive"))
      (node (ref "S2") (pin "3") (pintype "passive"))
      (node (ref "S2") (pin "4") (pintype "passive"))
      (node (ref "TP37") (pin "1") (pinfunction "1_1") (pintype "input"))
      (node (ref "TP38") (pin "1") (pinfunction "1_1") (pintype "input"))
      (node (ref "U13") (pin "3") (pinfunction "GND_3") (pintype "power_in"))
      (node (ref "U13") (pin "6") (pinfunction "GND_6") (pintype "power_in"))
      (node (ref "U14") (pin "1") (pinfunction "A1_1") (pintype "input"))
      (node (ref "U14") (pin "7") (pinfunction "GND_7") (pintype "power_in"))
    )
    (net (code "41") (name "VCC_1V8") (class "Default")
      (node (ref "C81") (pin "1") (pinfunction "1_1") (pintype "passive"))
      (node (ref "C82") (pin "2") (pinfunction "2_2") (pintype "passive"))
      (node (ref "C83") (pin "2") (pinfunction "2_2") (pintype "passive"))
      (node (ref "C84") (pin "2") (pinfunction "2_2") (pintype "passive"))
      (node (ref "R31") (pin "2") (pinfunction "2_2") (pintype "passive"))
    )
    (net (code "42") (name "VCC_IO_B34") (class "Default")
      (node (ref "C56") (pin "2") (pinfunction "2_2") (pintype "passive"))
      (node (ref "C66") (pin "1") (pinfunction "1_1") (pintype "passive"))
      (node (ref "C67") (pin "2") (pinfunction "2_2") (pintype "passive"))
      (node (ref "C68") (pin "2") (pinfunction "2_2") (pintype "passive"))
      (node (ref "C69") (pin "2") (pinfunction "2_2") (pintype "passive"))
      (node (ref "C70") (pin "1") (pinfunction "1_1") (pintype "passive"))
      (node (ref "C71") (pin "2") (pinfunction "2_2") (pintype "passive"))
      (node (ref "C72") (pin "2") (pinfunction "2_2") (pintype "passive"))
      (node (ref "C73") (pin "2") (pinfunction "2_2") (pintype "passive"))
      (node (ref "Q5") (pin "2") (pinfunction "Gate_2") (pintype "passive"))
      (node (ref "Q5") (pin "5") (pinfunction "Gate_5") (pintype "passive"))
      (node (ref "R25") (pin "1") (pinfunction "1_1") (pintype "passive"))
      (node (ref "R26") (pin "1") (pinfunction "1_1") (pintype "passive"))
      (node (ref "TP35") (pin "1") (pinfunction "1_1") (pintype "input"))
      (node (ref "U13") (pin "4") (pinfunction "OUT_4") (pintype "power_in"))
    )
    (net (code "43") (name "VDD_MARS_3V3") (class "Default")
      (node (ref "C51") (pin "2") (pinfunction "2_2") (pintype "passive"))
      (node (ref "C52") (pin "1") (pinfunction "1_1") (pintype "passive"))
      (node (ref "C53") (pin "1") (pinfunction "1_1") (pintype "passive"))
      (node (ref "C77") (pin "1") (pinfunction "1_1") (pintype "passive"))
      (node (ref "C78") (pin "2") (pinfunction "2_2") (pintype "passive"))
      (node (ref "C79") (pin "2") (pinfunction "2_2") (pintype "passive"))
      (node (ref "C80") (pin "2") (pinfunction "2_2") (pintype "passive"))
      (node (ref "D20") (pin "2") (pinfunction "A_2") (pintype "passive"))
      (node (ref "D21") (pin "1") (pinfunction "1_1") (pintype "passive"))
      (node (ref "D22") (pin "2") (pinfunction "A_2") (pintype "passive"))
      (node (ref "FB5") (pin "2") (pinfunction "2_2") (pintype "passive"))
      (node (ref "R21") (pin "1") (pinfunction "1_1") (pintype "passive"))
      (node (ref "TP36") (pin "1") (pinfunction "1_1") (pintype "input"))
      (node (ref "U13") (pin "2") (pinfunction "IN_2") (pintype "power_in"))
    )
  )
)
